# design.net
KiCad netlist of a schematic drawn in Altium Designer
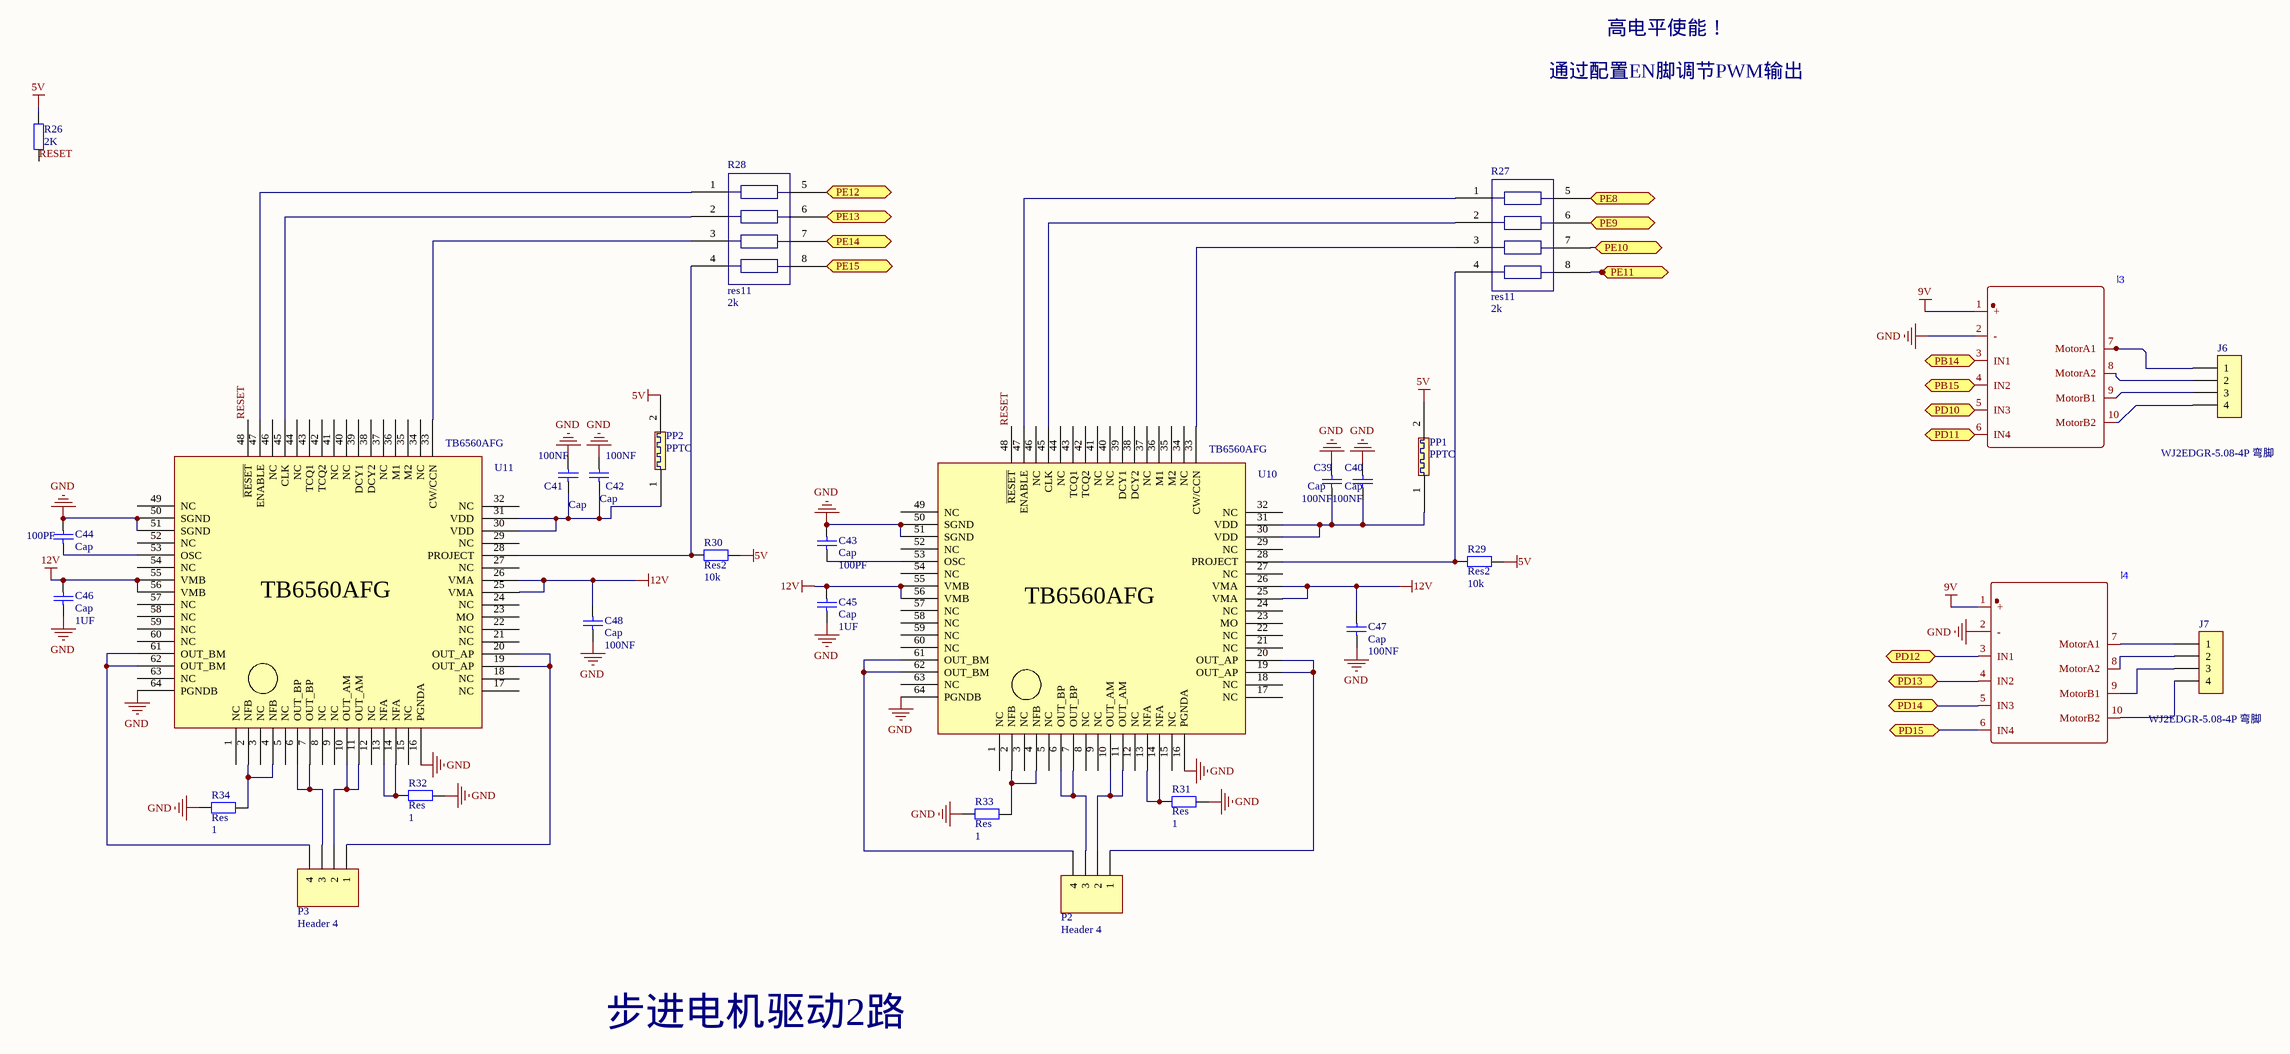
[diagram p0: 电机驱动&步进电机驱动.SchDoc]

(export (version "E")
  (design (tool "Eeschema 10.0.6"))
  (components
    (comp (ref "C39")
      (value "Cap")
      (footprint "0805_C")
      (description "Capacitor")
      (fields (field (name "ALTIUM_VALUE") "100NF") (field (name "PUBLISHER") "Altium Limited"))
      (libsource (lib "Miscellaneous Devices") (part "Cap"))
    )
    (comp (ref "C40")
      (value "Cap")
      (footprint "0805_C")
      (description "Capacitor")
      (fields (field (name "ALTIUM_VALUE") "100NF") (field (name "PUBLISHER") "Altium Limited"))
      (libsource (lib "Miscellaneous Devices") (part "Cap"))
    )
    (comp (ref "C41")
      (value "Cap")
      (footprint "0805_C")
      (description "Capacitor")
      (fields (field (name "ALTIUM_VALUE") "100NF") (field (name "PUBLISHER") "Altium Limited"))
      (libsource (lib "Miscellaneous Devices") (part "Cap"))
    )
    (comp (ref "C42")
      (value "Cap")
      (footprint "0805_C")
      (description "Capacitor")
      (fields (field (name "ALTIUM_VALUE") "100NF") (field (name "PUBLISHER") "Altium Limited"))
      (libsource (lib "Miscellaneous Devices") (part "Cap"))
    )
    (comp (ref "C43")
      (value "Cap")
      (footprint "0805_C")
      (description "Capacitor")
      (fields (field (name "ALTIUM_VALUE") "100PF") (field (name "PUBLISHER") "Altium Limited"))
      (libsource (lib "Miscellaneous Devices") (part "Cap"))
    )
    (comp (ref "C44")
      (value "Cap")
      (footprint "0805_C")
      (description "Capacitor")
      (fields (field (name "ALTIUM_VALUE") "100PF") (field (name "PUBLISHER") "Altium Limited"))
      (libsource (lib "Miscellaneous Devices") (part "Cap"))
    )
    (comp (ref "C45")
      (value "Cap")
      (footprint "0805_C")
      (description "Capacitor")
      (fields (field (name "ALTIUM_VALUE") "1UF") (field (name "PUBLISHER") "Altium Limited"))
      (libsource (lib "Miscellaneous Devices") (part "Cap"))
    )
    (comp (ref "C46")
      (value "Cap")
      (footprint "0805_C")
      (description "Capacitor")
      (fields (field (name "ALTIUM_VALUE") "1UF") (field (name "PUBLISHER") "Altium Limited"))
      (libsource (lib "Miscellaneous Devices") (part "Cap"))
    )
    (comp (ref "C47")
      (value "Cap")
      (footprint "0805_C")
      (description "Capacitor")
      (fields (field (name "ALTIUM_VALUE") "100NF") (field (name "PUBLISHER") "Altium Limited"))
      (libsource (lib "Miscellaneous Devices") (part "Cap"))
    )
    (comp (ref "C48")
      (value "Cap")
      (footprint "0805_C")
      (description "Capacitor")
      (fields (field (name "ALTIUM_VALUE") "100NF") (field (name "PUBLISHER") "Altium Limited"))
      (libsource (lib "Miscellaneous Devices") (part "Cap"))
    )
    (comp (ref "J6")
      (value "WJ2EDGR-5.08-4P 弯脚")
      (footprint "Connector:WJ2EDGR-5.08-4")
      (description "2EDG连接器")
      (libsource (lib "Connector") (part "WJ2EDGR-5.08-4P 弯脚"))
    )
    (comp (ref "J7")
      (value "WJ2EDGR-5.08-4P 弯脚")
      (footprint "Connector:WJ2EDGR-5.08-4")
      (description "2EDG连接器")
      (libsource (lib "Connector") (part "WJ2EDGR-5.08-4P 弯脚"))
    )
    (comp (ref "l3")
      (value "~")
      (footprint "L298N_MINI")
      (libsource (lib "altium-import") (part "root_0_l298n_mini_"))
    )
    (comp (ref "l4")
      (value "~")
      (footprint "L298N_MINI")
      (libsource (lib "altium-import") (part "root_0_l298n_mini_"))
    )
    (comp (ref "P2")
      (value "Header 4")
      (footprint "WJ2EDGR-5.08-4")
      (description "Header, 4-Pin")
      (fields (field (name "PUBLISHER") "Altium Limited"))
      (libsource (lib "Miscellaneous Connectors") (part "Header 4"))
    )
    (comp (ref "P3")
      (value "Header 4")
      (footprint "WJ2EDGR-5.08-4")
      (description "Header, 4-Pin")
      (fields (field (name "PUBLISHER") "Altium Limited"))
      (libsource (lib "Miscellaneous Connectors") (part "Header 4"))
    )
    (comp (ref "PP1") (value "PPTC") (footprint "1206") (libsource (lib "TB6560AFG") (part "PPTC")))
    (comp (ref "PP2") (value "PPTC") (footprint "1206") (libsource (lib "TB6560AFG") (part "PPTC")))
    (comp (ref "R26")
      (value "2K")
      (footprint "0805")
      (description "Resistor")
      (fields (field (name "Comment") "Res2") (field (name "PUBLISHER") "Altium Limited"))
      (libsource (lib "") (part "Res2_1"))
    )
    (comp (ref "R27")
      (value "res11")
      (footprint "RES_PACK4")
      (fields (field (name "ALTIUM_VALUE") "2k"))
      (libsource (lib "TB6560AFG") (part "res11"))
    )
    (comp (ref "R28")
      (value "res11")
      (footprint "RES_PACK4")
      (fields (field (name "ALTIUM_VALUE") "2k"))
      (libsource (lib "TB6560AFG") (part "res11"))
    )
    (comp (ref "R29")
      (value "Res2")
      (footprint "0805")
      (description "Resistor")
      (fields (field (name "ALTIUM_VALUE") "10k") (field (name "PUBLISHER") "Altium Limited"))
      (libsource (lib "Miscellaneous Devices") (part "Res2"))
    )
    (comp (ref "R30")
      (value "Res2")
      (footprint "0805")
      (description "Resistor")
      (fields (field (name "ALTIUM_VALUE") "10k") (field (name "PUBLISHER") "Altium Limited"))
      (libsource (lib "Miscellaneous Devices") (part "Res2"))
    )
    (comp (ref "R31")
      (value "Res")
      (footprint "2512")
      (description "Resistor")
      (fields (field (name "ALTIUM_VALUE") "1") (field (name "PUBLISHER") "Altium Limited"))
      (libsource (lib "Miscellaneous Devices") (part "Res2"))
    )
    (comp (ref "R32")
      (value "Res")
      (footprint "2512")
      (description "Resistor")
      (fields (field (name "ALTIUM_VALUE") "1") (field (name "PUBLISHER") "Altium Limited"))
      (libsource (lib "Miscellaneous Devices") (part "Res2"))
    )
    (comp (ref "R33")
      (value "Res")
      (footprint "2512")
      (description "Resistor")
      (fields (field (name "ALTIUM_VALUE") "1") (field (name "PUBLISHER") "Altium Limited"))
      (libsource (lib "Miscellaneous Devices") (part "Res2"))
    )
    (comp (ref "R34")
      (value "Res")
      (footprint "2512")
      (description "Resistor")
      (fields (field (name "ALTIUM_VALUE") "1") (field (name "PUBLISHER") "Altium Limited"))
      (libsource (lib "Miscellaneous Devices") (part "Res2"))
    )
    (comp (ref "U10")
      (value "TB6560AFG")
      (footprint "TB6560AFG")
      (libsource (lib "TB6560AFG") (part "TB6560AFG"))
    )
    (comp (ref "U11")
      (value "TB6560AFG")
      (footprint "TB6560AFG")
      (libsource (lib "TB6560AFG") (part "TB6560AFG"))
    )
  )
  (nets
    (net (code "1") (name "/PB14") (class "Default")
      (node (ref "l3") (pin "3") (pinfunction "IN1_3") (pintype "passive"))
    )
    (net (code "2") (name "/PB15") (class "Default")
      (node (ref "l3") (pin "4") (pinfunction "IN2_4") (pintype "passive"))
    )
    (net (code "3") (name "/PD10") (class "Default")
      (node (ref "l3") (pin "5") (pinfunction "IN3_5") (pintype "passive"))
    )
    (net (code "4") (name "/PD11") (class "Default")
      (node (ref "l3") (pin "6") (pinfunction "IN4_6") (pintype "passive"))
    )
    (net (code "5") (name "/PD12") (class "Default")
      (node (ref "l4") (pin "3") (pinfunction "IN1_3") (pintype "passive"))
    )
    (net (code "6") (name "/PD13") (class "Default")
      (node (ref "l4") (pin "4") (pinfunction "IN2_4") (pintype "passive"))
    )
    (net (code "7") (name "/PD14") (class "Default")
      (node (ref "l4") (pin "5") (pinfunction "IN3_5") (pintype "passive"))
    )
    (net (code "8") (name "/PD15") (class "Default")
      (node (ref "l4") (pin "6") (pinfunction "IN4_6") (pintype "passive"))
    )
    (net (code "9") (name "/PE8") (class "Default")
      (node (ref "R27") (pin "5") (pinfunction "PGNDB_5") (pintype "passive"))
    )
    (net (code "10") (name "/PE9") (class "Default")
      (node (ref "R27") (pin "6") (pinfunction "PGNDB_6") (pintype "passive"))
    )
    (net (code "11") (name "/PE10") (class "Default")
      (node (ref "R27") (pin "7") (pinfunction "PGNDB_7") (pintype "passive"))
    )
    (net (code "12") (name "/PE11") (class "Default")
      (node (ref "R27") (pin "8") (pinfunction "PGNDB_8") (pintype "passive"))
    )
    (net (code "13") (name "/PE12") (class "Default")
      (node (ref "R28") (pin "5") (pinfunction "PGNDB_5") (pintype "passive"))
    )
    (net (code "14") (name "/PE13") (class "Default")
      (node (ref "R28") (pin "6") (pinfunction "PGNDB_6") (pintype "passive"))
    )
    (net (code "15") (name "/PE14") (class "Default")
      (node (ref "R28") (pin "7") (pinfunction "PGNDB_7") (pintype "passive"))
    )
    (net (code "16") (name "/PE15") (class "Default")
      (node (ref "R28") (pin "8") (pinfunction "PGNDB_8") (pintype "passive"))
    )
    (net (code "17") (name "/RESET") (class "Default")
      (node (ref "R26") (pin "2") (pinfunction "2_2") (pintype "passive"))
      (node (ref "U10") (pin "48") (pinfunction "~{RESET}_48") (pintype "passive"))
      (node (ref "U11") (pin "48") (pinfunction "~{RESET}_48") (pintype "passive"))
    )
    (net (code "18") (name "5V") (class "Default")
      (node (ref "PP1") (pin "2") (pinfunction "B_2") (pintype "passive"))
      (node (ref "PP2") (pin "2") (pinfunction "B_2") (pintype "passive"))
      (node (ref "R26") (pin "1") (pinfunction "1_1") (pintype "passive"))
      (node (ref "R29") (pin "1") (pinfunction "1_1") (pintype "passive"))
      (node (ref "R30") (pin "1") (pinfunction "1_1") (pintype "passive"))
    )
    (net (code "19") (name "9V") (class "Default")
      (node (ref "l3") (pin "1") (pinfunction "+_1") (pintype "passive"))
      (node (ref "l4") (pin "1") (pinfunction "+_1") (pintype "passive"))
    )
    (net (code "20") (name "12V") (class "Default")
      (node (ref "C45") (pin "2") (pinfunction "2_2") (pintype "passive"))
      (node (ref "C46") (pin "2") (pinfunction "2_2") (pintype "passive"))
      (node (ref "C47") (pin "1") (pinfunction "1_1") (pintype "passive"))
      (node (ref "C48") (pin "1") (pinfunction "1_1") (pintype "passive"))
      (node (ref "U10") (pin "25") (pinfunction "VMA_25") (pintype "passive"))
      (node (ref "U10") (pin "26") (pinfunction "VMA_26") (pintype "passive"))
      (node (ref "U10") (pin "55") (pinfunction "VMB_55") (pintype "passive"))
      (node (ref "U10") (pin "56") (pinfunction "VMB_56") (pintype "passive"))
      (node (ref "U11") (pin "25") (pinfunction "VMA_25") (pintype "passive"))
      (node (ref "U11") (pin "26") (pinfunction "VMA_26") (pintype "passive"))
      (node (ref "U11") (pin "55") (pinfunction "VMB_55") (pintype "passive"))
      (node (ref "U11") (pin "56") (pinfunction "VMB_56") (pintype "passive"))
    )
    (net (code "21") (name "GND") (class "Default")
      (node (ref "C39") (pin "2") (pinfunction "2_2") (pintype "passive"))
      (node (ref "C40") (pin "2") (pinfunction "2_2") (pintype "passive"))
      (node (ref "C41") (pin "2") (pinfunction "2_2") (pintype "passive"))
      (node (ref "C42") (pin "2") (pinfunction "2_2") (pintype "passive"))
      (node (ref "C43") (pin "2") (pinfunction "2_2") (pintype "passive"))
      (node (ref "C44") (pin "2") (pinfunction "2_2") (pintype "passive"))
      (node (ref "C45") (pin "1") (pinfunction "1_1") (pintype "passive"))
      (node (ref "C46") (pin "1") (pinfunction "1_1") (pintype "passive"))
      (node (ref "C47") (pin "2") (pinfunction "2_2") (pintype "passive"))
      (node (ref "C48") (pin "2") (pinfunction "2_2") (pintype "passive"))
      (node (ref "R31") (pin "1") (pinfunction "1_1") (pintype "passive"))
      (node (ref "R32") (pin "1") (pinfunction "1_1") (pintype "passive"))
      (node (ref "R33") (pin "2") (pinfunction "2_2") (pintype "passive"))
      (node (ref "R34") (pin "2") (pinfunction "2_2") (pintype "passive"))
      (node (ref "U10") (pin "16") (pinfunction "PGNDA_16") (pintype "passive"))
      (node (ref "U10") (pin "50") (pinfunction "SGND_50") (pintype "passive"))
      (node (ref "U10") (pin "51") (pinfunction "SGND_51") (pintype "passive"))
      (node (ref "U10") (pin "64") (pinfunction "PGNDB_64") (pintype "passive"))
      (node (ref "U11") (pin "16") (pinfunction "PGNDA_16") (pintype "passive"))
      (node (ref "U11") (pin "50") (pinfunction "SGND_50") (pintype "passive"))
      (node (ref "U11") (pin "51") (pinfunction "SGND_51") (pintype "passive"))
      (node (ref "U11") (pin "64") (pinfunction "PGNDB_64") (pintype "passive"))
      (node (ref "l3") (pin "2") (pinfunction "-_2") (pintype "passive"))
      (node (ref "l4") (pin "2") (pinfunction "-_2") (pintype "passive"))
    )
    (net (code "22") (name "Net-(C39-Pad1)") (class "Default")
      (node (ref "C39") (pin "1") (pinfunction "1_1") (pintype "passive"))
      (node (ref "C40") (pin "1") (pinfunction "1_1") (pintype "passive"))
      (node (ref "PP1") (pin "1") (pinfunction "B_1") (pintype "passive"))
      (node (ref "U10") (pin "30") (pinfunction "VDD_30") (pintype "passive"))
      (node (ref "U10") (pin "31") (pinfunction "VDD_31") (pintype "passive"))
    )
    (net (code "23") (name "Net-(C41-Pad1)") (class "Default")
      (node (ref "C41") (pin "1") (pinfunction "1_1") (pintype "passive"))
      (node (ref "C42") (pin "1") (pinfunction "1_1") (pintype "passive"))
      (node (ref "PP2") (pin "1") (pinfunction "B_1") (pintype "passive"))
      (node (ref "U11") (pin "30") (pinfunction "VDD_30") (pintype "passive"))
      (node (ref "U11") (pin "31") (pinfunction "VDD_31") (pintype "passive"))
    )
    (net (code "24") (name "Net-(P2-Pad1)") (class "Default")
      (node (ref "P2") (pin "1") (pinfunction "1_1") (pintype "passive"))
      (node (ref "U10") (pin "19") (pinfunction "OUT_AP_19") (pintype "passive"))
      (node (ref "U10") (pin "20") (pinfunction "OUT_AP_20") (pintype "passive"))
    )
    (net (code "25") (name "Net-(P2-Pad2)") (class "Default")
      (node (ref "P2") (pin "2") (pinfunction "2_2") (pintype "passive"))
      (node (ref "U10") (pin "10") (pinfunction "OUT_AM_10") (pintype "passive"))
      (node (ref "U10") (pin "11") (pinfunction "OUT_AM_11") (pintype "passive"))
    )
    (net (code "26") (name "Net-(P2-Pad3)") (class "Default")
      (node (ref "P2") (pin "3") (pinfunction "3_3") (pintype "passive"))
      (node (ref "U10") (pin "6") (pinfunction "OUT_BP_6") (pintype "passive"))
      (node (ref "U10") (pin "7") (pinfunction "OUT_BP_7") (pintype "passive"))
    )
    (net (code "27") (name "Net-(P2-Pad4)") (class "Default")
      (node (ref "P2") (pin "4") (pinfunction "4_4") (pintype "passive"))
      (node (ref "U10") (pin "61") (pinfunction "OUT_BM_61") (pintype "passive"))
      (node (ref "U10") (pin "62") (pinfunction "OUT_BM_62") (pintype "passive"))
    )
    (net (code "28") (name "Net-(P3-Pad1)") (class "Default")
      (node (ref "P3") (pin "1") (pinfunction "1_1") (pintype "passive"))
      (node (ref "U11") (pin "19") (pinfunction "OUT_AP_19") (pintype "passive"))
      (node (ref "U11") (pin "20") (pinfunction "OUT_AP_20") (pintype "passive"))
    )
    (net (code "29") (name "Net-(P3-Pad2)") (class "Default")
      (node (ref "P3") (pin "2") (pinfunction "2_2") (pintype "passive"))
      (node (ref "U11") (pin "10") (pinfunction "OUT_AM_10") (pintype "passive"))
      (node (ref "U11") (pin "11") (pinfunction "OUT_AM_11") (pintype "passive"))
    )
    (net (code "30") (name "Net-(P3-Pad3)") (class "Default")
      (node (ref "P3") (pin "3") (pinfunction "3_3") (pintype "passive"))
      (node (ref "U11") (pin "6") (pinfunction "OUT_BP_6") (pintype "passive"))
      (node (ref "U11") (pin "7") (pinfunction "OUT_BP_7") (pintype "passive"))
    )
    (net (code "31") (name "Net-(P3-Pad4)") (class "Default")
      (node (ref "P3") (pin "4") (pinfunction "4_4") (pintype "passive"))
      (node (ref "U11") (pin "61") (pinfunction "OUT_BM_61") (pintype "passive"))
      (node (ref "U11") (pin "62") (pinfunction "OUT_BM_62") (pintype "passive"))
    )
    (net (code "32") (name "Net-(R31-Pad2)") (class "Default")
      (node (ref "R31") (pin "2") (pinfunction "2_2") (pintype "passive"))
      (node (ref "U10") (pin "13") (pinfunction "NFA_13") (pintype "passive"))
      (node (ref "U10") (pin "14") (pinfunction "NFA_14") (pintype "passive"))
    )
    (net (code "33") (name "Net-(R32-Pad2)") (class "Default")
      (node (ref "R32") (pin "2") (pinfunction "2_2") (pintype "passive"))
      (node (ref "U11") (pin "13") (pinfunction "NFA_13") (pintype "passive"))
      (node (ref "U11") (pin "14") (pinfunction "NFA_14") (pintype "passive"))
    )
    (net (code "34") (name "Net-(R33-Pad1)") (class "Default")
      (node (ref "R33") (pin "1") (pinfunction "1_1") (pintype "passive"))
      (node (ref "U10") (pin "2") (pinfunction "NFB_2") (pintype "passive"))
      (node (ref "U10") (pin "4") (pinfunction "NFB_4") (pintype "passive"))
    )
    (net (code "35") (name "Net-(R34-Pad1)") (class "Default")
      (node (ref "R34") (pin "1") (pinfunction "1_1") (pintype "passive"))
      (node (ref "U11") (pin "2") (pinfunction "NFB_2") (pintype "passive"))
      (node (ref "U11") (pin "4") (pinfunction "NFB_4") (pintype "passive"))
    )
    (net (code "36") (name "Net-(U10-CLK)") (class "Default")
      (node (ref "R27") (pin "2") (pinfunction "PGNDB_2") (pintype "passive"))
      (node (ref "U10") (pin "45") (pinfunction "CLK_45") (pintype "passive"))
    )
    (net (code "37") (name "Net-(U10-CW{slash}CCN)") (class "Default")
      (node (ref "R27") (pin "3") (pinfunction "PGNDB_3") (pintype "passive"))
      (node (ref "U10") (pin "33") (pinfunction "CW/CCN_33") (pintype "passive"))
    )
    (net (code "38") (name "Net-(U10-ENABLE)") (class "Default")
      (node (ref "R27") (pin "1") (pinfunction "PGNDB_1") (pintype "passive"))
      (node (ref "U10") (pin "47") (pinfunction "ENABLE_47") (pintype "passive"))
    )
    (net (code "39") (name "Net-(U10-OSC)") (class "Default")
      (node (ref "C43") (pin "1") (pinfunction "1_1") (pintype "passive"))
      (node (ref "U10") (pin "53") (pinfunction "OSC_53") (pintype "passive"))
    )
    (net (code "40") (name "Net-(U10-PROJECT)") (class "Default")
      (node (ref "R27") (pin "4") (pinfunction "PGNDB_4") (pintype "passive"))
      (node (ref "R29") (pin "2") (pinfunction "2_2") (pintype "passive"))
      (node (ref "U10") (pin "28") (pinfunction "PROJECT_28") (pintype "passive"))
    )
    (net (code "41") (name "Net-(U11-CLK)") (class "Default")
      (node (ref "R28") (pin "2") (pinfunction "PGNDB_2") (pintype "passive"))
      (node (ref "U11") (pin "45") (pinfunction "CLK_45") (pintype "passive"))
    )
    (net (code "42") (name "Net-(U11-CW{slash}CCN)") (class "Default")
      (node (ref "R28") (pin "3") (pinfunction "PGNDB_3") (pintype "passive"))
      (node (ref "U11") (pin "33") (pinfunction "CW/CCN_33") (pintype "passive"))
    )
    (net (code "43") (name "Net-(U11-ENABLE)") (class "Default")
      (node (ref "R28") (pin "1") (pinfunction "PGNDB_1") (pintype "passive"))
      (node (ref "U11") (pin "47") (pinfunction "ENABLE_47") (pintype "passive"))
    )
    (net (code "44") (name "Net-(U11-OSC)") (class "Default")
      (node (ref "C44") (pin "1") (pinfunction "1_1") (pintype "passive"))
      (node (ref "U11") (pin "53") (pinfunction "OSC_53") (pintype "passive"))
    )
    (net (code "45") (name "Net-(U11-PROJECT)") (class "Default")
      (node (ref "R28") (pin "4") (pinfunction "PGNDB_4") (pintype "passive"))
      (node (ref "R30") (pin "2") (pinfunction "2_2") (pintype "passive"))
      (node (ref "U11") (pin "28") (pinfunction "PROJECT_28") (pintype "passive"))
    )
    (net (code "46") (name "Net-(l3-MotorA1)") (class "Default")
      (node (ref "J6") (pin "1") (pinfunction "1_1") (pintype "passive"))
      (node (ref "l3") (pin "7") (pinfunction "MotorA1_7") (pintype "passive"))
    )
    (net (code "47") (name "Net-(l3-MotorA2)") (class "Default")
      (node (ref "J6") (pin "2") (pinfunction "2_2") (pintype "passive"))
      (node (ref "l3") (pin "8") (pinfunction "MotorA2_8") (pintype "passive"))
    )
    (net (code "48") (name "Net-(l3-MotorB1)") (class "Default")
      (node (ref "J6") (pin "3") (pinfunction "3_3") (pintype "passive"))
      (node (ref "l3") (pin "9") (pinfunction "MotorB1_9") (pintype "passive"))
    )
    (net (code "49") (name "Net-(l3-MotorB2)") (class "Default")
      (node (ref "J6") (pin "4") (pinfunction "4_4") (pintype "passive"))
      (node (ref "l3") (pin "10") (pinfunction "MotorB2_10") (pintype "passive"))
    )
    (net (code "50") (name "Net-(l4-MotorA1)") (class "Default")
      (node (ref "J7") (pin "1") (pinfunction "1_1") (pintype "passive"))
      (node (ref "l4") (pin "7") (pinfunction "MotorA1_7") (pintype "passive"))
    )
    (net (code "51") (name "Net-(l4-MotorA2)") (class "Default")
      (node (ref "J7") (pin "2") (pinfunction "2_2") (pintype "passive"))
      (node (ref "l4") (pin "8") (pinfunction "MotorA2_8") (pintype "passive"))
    )
    (net (code "52") (name "Net-(l4-MotorB1)") (class "Default")
      (node (ref "J7") (pin "3") (pinfunction "3_3") (pintype "passive"))
      (node (ref "l4") (pin "9") (pinfunction "MotorB1_9") (pintype "passive"))
    )
    (net (code "53") (name "Net-(l4-MotorB2)") (class "Default")
      (node (ref "J7") (pin "4") (pinfunction "4_4") (pintype "passive"))
      (node (ref "l4") (pin "10") (pinfunction "MotorB2_10") (pintype "passive"))
    )
    (net (code "54") (name "unconnected-(U10-DCY1-Pad39)") (class "Default")
      (node (ref "U10") (pin "39") (pinfunction "DCY1_39") (pintype "passive"))
    )
    (net (code "55") (name "unconnected-(U10-DCY2-Pad38)") (class "Default")
      (node (ref "U10") (pin "38") (pinfunction "DCY2_38") (pintype "passive"))
    )
    (net (code "56") (name "unconnected-(U10-M1-Pad36)") (class "Default")
      (node (ref "U10") (pin "36") (pinfunction "M1_36") (pintype "passive"))
    )
    (net (code "57") (name "unconnected-(U10-M2-Pad35)") (class "Default")
      (node (ref "U10") (pin "35") (pinfunction "M2_35") (pintype "passive"))
    )
    (net (code "58") (name "unconnected-(U10-MO-Pad23)") (class "Default")
      (node (ref "U10") (pin "23") (pinfunction "MO_23") (pintype "passive"))
    )
    (net (code "59") (name "unconnected-(U10-NC-Pad1)") (class "Default")
      (node (ref "U10") (pin "1") (pinfunction "NC_1") (pintype "passive"))
    )
    (net (code "60") (name "unconnected-(U10-NC-Pad3)") (class "Default")
      (node (ref "U10") (pin "3") (pinfunction "NC_3") (pintype "passive"))
    )
    (net (code "61") (name "unconnected-(U10-NC-Pad5)") (class "Default")
      (node (ref "U10") (pin "5") (pinfunction "NC_5") (pintype "passive"))
    )
    (net (code "62") (name "unconnected-(U10-NC-Pad8)") (class "Default")
      (node (ref "U10") (pin "8") (pinfunction "NC_8") (pintype "passive"))
    )
    (net (code "63") (name "unconnected-(U10-NC-Pad9)") (class "Default")
      (node (ref "U10") (pin "9") (pinfunction "NC_9") (pintype "passive"))
    )
    (net (code "64") (name "unconnected-(U10-NC-Pad12)") (class "Default")
      (node (ref "U10") (pin "12") (pinfunction "NC_12") (pintype "passive"))
    )
    (net (code "65") (name "unconnected-(U10-NC-Pad15)") (class "Default")
      (node (ref "U10") (pin "15") (pinfunction "NC_15") (pintype "passive"))
    )
    (net (code "66") (name "unconnected-(U10-NC-Pad17)") (class "Default")
      (node (ref "U10") (pin "17") (pinfunction "NC_17") (pintype "passive"))
    )
    (net (code "67") (name "unconnected-(U10-NC-Pad18)") (class "Default")
      (node (ref "U10") (pin "18") (pinfunction "NC_18") (pintype "passive"))
    )
    (net (code "68") (name "unconnected-(U10-NC-Pad21)") (class "Default")
      (node (ref "U10") (pin "21") (pinfunction "NC_21") (pintype "passive"))
    )
    (net (code "69") (name "unconnected-(U10-NC-Pad22)") (class "Default")
      (node (ref "U10") (pin "22") (pinfunction "NC_22") (pintype "passive"))
    )
    (net (code "70") (name "unconnected-(U10-NC-Pad24)") (class "Default")
      (node (ref "U10") (pin "24") (pinfunction "NC_24") (pintype "passive"))
    )
    (net (code "71") (name "unconnected-(U10-NC-Pad27)") (class "Default")
      (node (ref "U10") (pin "27") (pinfunction "NC_27") (pintype "passive"))
    )
    (net (code "72") (name "unconnected-(U10-NC-Pad29)") (class "Default")
      (node (ref "U10") (pin "29") (pinfunction "NC_29") (pintype "passive"))
    )
    (net (code "73") (name "unconnected-(U10-NC-Pad32)") (class "Default")
      (node (ref "U10") (pin "32") (pinfunction "NC_32") (pintype "passive"))
    )
    (net (code "74") (name "unconnected-(U10-NC-Pad34)") (class "Default")
      (node (ref "U10") (pin "34") (pinfunction "NC_34") (pintype "passive"))
    )
    (net (code "75") (name "unconnected-(U10-NC-Pad37)") (class "Default")
      (node (ref "U10") (pin "37") (pinfunction "NC_37") (pintype "passive"))
    )
    (net (code "76") (name "unconnected-(U10-NC-Pad40)") (class "Default")
      (node (ref "U10") (pin "40") (pinfunction "NC_40") (pintype "passive"))
    )
    (net (code "77") (name "unconnected-(U10-NC-Pad41)") (class "Default")
      (node (ref "U10") (pin "41") (pinfunction "NC_41") (pintype "passive"))
    )
    (net (code "78") (name "unconnected-(U10-NC-Pad44)") (class "Default")
      (node (ref "U10") (pin "44") (pinfunction "NC_44") (pintype "passive"))
    )
    (net (code "79") (name "unconnected-(U10-NC-Pad46)") (class "Default")
      (node (ref "U10") (pin "46") (pinfunction "NC_46") (pintype "passive"))
    )
    (net (code "80") (name "unconnected-(U10-NC-Pad49)") (class "Default")
      (node (ref "U10") (pin "49") (pinfunction "NC_49") (pintype "passive"))
    )
    (net (code "81") (name "unconnected-(U10-NC-Pad52)") (class "Default")
      (node (ref "U10") (pin "52") (pinfunction "NC_52") (pintype "passive"))
    )
    (net (code "82") (name "unconnected-(U10-NC-Pad54)") (class "Default")
      (node (ref "U10") (pin "54") (pinfunction "NC_54") (pintype "passive"))
    )
    (net (code "83") (name "unconnected-(U10-NC-Pad57)") (class "Default")
      (node (ref "U10") (pin "57") (pinfunction "NC_57") (pintype "passive"))
    )
    (net (code "84") (name "unconnected-(U10-NC-Pad58)") (class "Default")
      (node (ref "U10") (pin "58") (pinfunction "NC_58") (pintype "passive"))
    )
    (net (code "85") (name "unconnected-(U10-NC-Pad59)") (class "Default")
      (node (ref "U10") (pin "59") (pinfunction "NC_59") (pintype "passive"))
    )
    (net (code "86") (name "unconnected-(U10-NC-Pad60)") (class "Default")
      (node (ref "U10") (pin "60") (pinfunction "NC_60") (pintype "passive"))
    )
    (net (code "87") (name "unconnected-(U10-NC-Pad63)") (class "Default")
      (node (ref "U10") (pin "63") (pinfunction "NC_63") (pintype "passive"))
    )
    (net (code "88") (name "unconnected-(U10-TCQ1-Pad43)") (class "Default")
      (node (ref "U10") (pin "43") (pinfunction "TCQ1_43") (pintype "passive"))
    )
    (net (code "89") (name "unconnected-(U10-TCQ2-Pad42)") (class "Default")
      (node (ref "U10") (pin "42") (pinfunction "TCQ2_42") (pintype "passive"))
    )
    (net (code "90") (name "unconnected-(U11-DCY1-Pad39)") (class "Default")
      (node (ref "U11") (pin "39") (pinfunction "DCY1_39") (pintype "passive"))
    )
    (net (code "91") (name "unconnected-(U11-DCY2-Pad38)") (class "Default")
      (node (ref "U11") (pin "38") (pinfunction "DCY2_38") (pintype "passive"))
    )
    (net (code "92") (name "unconnected-(U11-M1-Pad36)") (class "Default")
      (node (ref "U11") (pin "36") (pinfunction "M1_36") (pintype "passive"))
    )
    (net (code "93") (name "unconnected-(U11-M2-Pad35)") (class "Default")
      (node (ref "U11") (pin "35") (pinfunction "M2_35") (pintype "passive"))
    )
    (net (code "94") (name "unconnected-(U11-MO-Pad23)") (class "Default")
      (node (ref "U11") (pin "23") (pinfunction "MO_23") (pintype "passive"))
    )
    (net (code "95") (name "unconnected-(U11-NC-Pad1)") (class "Default")
      (node (ref "U11") (pin "1") (pinfunction "NC_1") (pintype "passive"))
    )
    (net (code "96") (name "unconnected-(U11-NC-Pad3)") (class "Default")
      (node (ref "U11") (pin "3") (pinfunction "NC_3") (pintype "passive"))
    )
    (net (code "97") (name "unconnected-(U11-NC-Pad5)") (class "Default")
      (node (ref "U11") (pin "5") (pinfunction "NC_5") (pintype "passive"))
    )
    (net (code "98") (name "unconnected-(U11-NC-Pad8)") (class "Default")
      (node (ref "U11") (pin "8") (pinfunction "NC_8") (pintype "passive"))
    )
    (net (code "99") (name "unconnected-(U11-NC-Pad9)") (class "Default")
      (node (ref "U11") (pin "9") (pinfunction "NC_9") (pintype "passive"))
    )
    (net (code "100") (name "unconnected-(U11-NC-Pad12)") (class "Default")
      (node (ref "U11") (pin "12") (pinfunction "NC_12") (pintype "passive"))
    )
    (net (code "101") (name "unconnected-(U11-NC-Pad15)") (class "Default")
      (node (ref "U11") (pin "15") (pinfunction "NC_15") (pintype "passive"))
    )
    (net (code "102") (name "unconnected-(U11-NC-Pad17)") (class "Default")
      (node (ref "U11") (pin "17") (pinfunction "NC_17") (pintype "passive"))
    )
    (net (code "103") (name "unconnected-(U11-NC-Pad18)") (class "Default")
      (node (ref "U11") (pin "18") (pinfunction "NC_18") (pintype "passive"))
    )
    (net (code "104") (name "unconnected-(U11-NC-Pad21)") (class "Default")
      (node (ref "U11") (pin "21") (pinfunction "NC_21") (pintype "passive"))
    )
    (net (code "105") (name "unconnected-(U11-NC-Pad22)") (class "Default")
      (node (ref "U11") (pin "22") (pinfunction "NC_22") (pintype "passive"))
    )
    (net (code "106") (name "unconnected-(U11-NC-Pad24)") (class "Default")
      (node (ref "U11") (pin "24") (pinfunction "NC_24") (pintype "passive"))
    )
    (net (code "107") (name "unconnected-(U11-NC-Pad27)") (class "Default")
      (node (ref "U11") (pin "27") (pinfunction "NC_27") (pintype "passive"))
    )
    (net (code "108") (name "unconnected-(U11-NC-Pad29)") (class "Default")
      (node (ref "U11") (pin "29") (pinfunction "NC_29") (pintype "passive"))
    )
    (net (code "109") (name "unconnected-(U11-NC-Pad32)") (class "Default")
      (node (ref "U11") (pin "32") (pinfunction "NC_32") (pintype "passive"))
    )
    (net (code "110") (name "unconnected-(U11-NC-Pad34)") (class "Default")
      (node (ref "U11") (pin "34") (pinfunction "NC_34") (pintype "passive"))
    )
    (net (code "111") (name "unconnected-(U11-NC-Pad37)") (class "Default")
      (node (ref "U11") (pin "37") (pinfunction "NC_37") (pintype "passive"))
    )
    (net (code "112") (name "unconnected-(U11-NC-Pad40)") (class "Default")
      (node (ref "U11") (pin "40") (pinfunction "NC_40") (pintype "passive"))
    )
    (net (code "113") (name "unconnected-(U11-NC-Pad41)") (class "Default")
      (node (ref "U11") (pin "41") (pinfunction "NC_41") (pintype "passive"))
    )
    (net (code "114") (name "unconnected-(U11-NC-Pad44)") (class "Default")
      (node (ref "U11") (pin "44") (pinfunction "NC_44") (pintype "passive"))
    )
    (net (code "115") (name "unconnected-(U11-NC-Pad46)") (class "Default")
      (node (ref "U11") (pin "46") (pinfunction "NC_46") (pintype "passive"))
    )
    (net (code "116") (name "unconnected-(U11-NC-Pad49)") (class "Default")
      (node (ref "U11") (pin "49") (pinfunction "NC_49") (pintype "passive"))
    )
    (net (code "117") (name "unconnected-(U11-NC-Pad52)") (class "Default")
      (node (ref "U11") (pin "52") (pinfunction "NC_52") (pintype "passive"))
    )
    (net (code "118") (name "unconnected-(U11-NC-Pad54)") (class "Default")
      (node (ref "U11") (pin "54") (pinfunction "NC_54") (pintype "passive"))
    )
    (net (code "119") (name "unconnected-(U11-NC-Pad57)") (class "Default")
      (node (ref "U11") (pin "57") (pinfunction "NC_57") (pintype "passive"))
    )
    (net (code "120") (name "unconnected-(U11-NC-Pad58)") (class "Default")
      (node (ref "U11") (pin "58") (pinfunction "NC_58") (pintype "passive"))
    )
    (net (code "121") (name "unconnected-(U11-NC-Pad59)") (class "Default")
      (node (ref "U11") (pin "59") (pinfunction "NC_59") (pintype "passive"))
    )
    (net (code "122") (name "unconnected-(U11-NC-Pad60)") (class "Default")
      (node (ref "U11") (pin "60") (pinfunction "NC_60") (pintype "passive"))
    )
    (net (code "123") (name "unconnected-(U11-NC-Pad63)") (class "Default")
      (node (ref "U11") (pin "63") (pinfunction "NC_63") (pintype "passive"))
    )
    (net (code "124") (name "unconnected-(U11-TCQ1-Pad43)") (class "Default")
      (node (ref "U11") (pin "43") (pinfunction "TCQ1_43") (pintype "passive"))
    )
    (net (code "125") (name "unconnected-(U11-TCQ2-Pad42)") (class "Default")
      (node (ref "U11") (pin "42") (pinfunction "TCQ2_42") (pintype "passive"))
    )
  )
)
